# MCU.net
KiCad netlist of a schematic drawn in Altium Designer
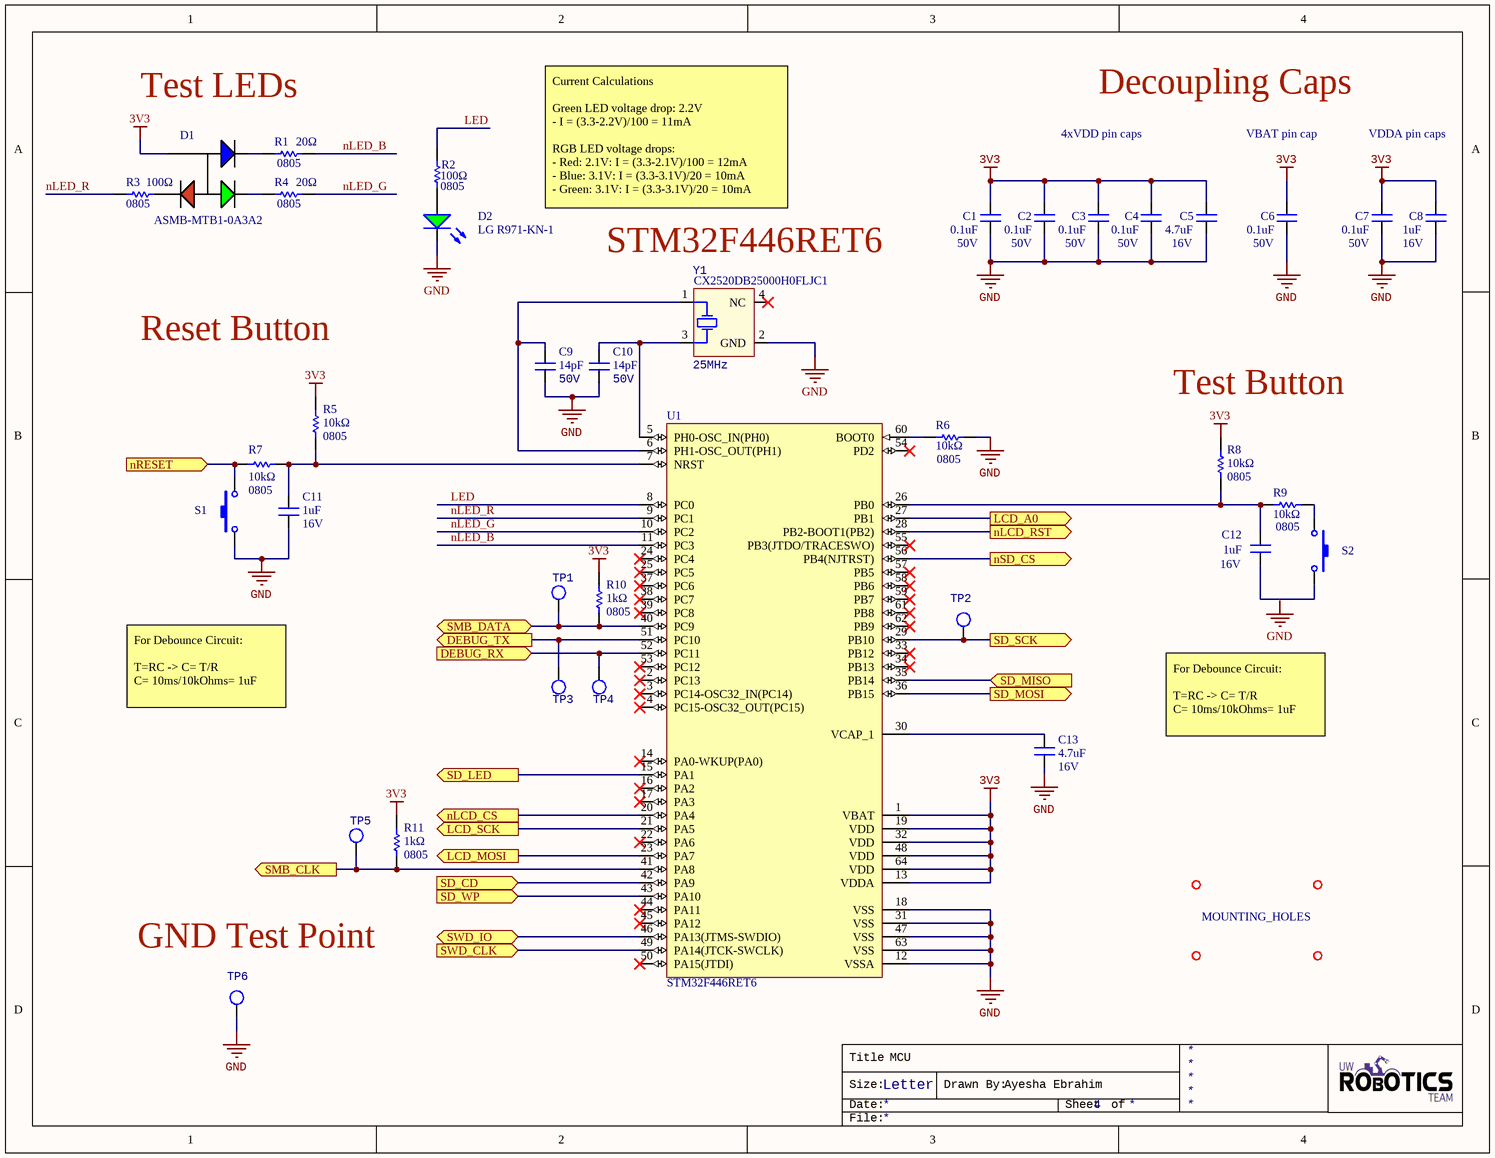
[diagram p0: MCU.SchDoc]

(export (version "E")
  (design (tool "Eeschema 10.0.6"))
  (components
    (comp (ref "C1")
      (value "0.1uF")
      (footprint "CAPC2012X140N")
      (description "CAP CER 0.1UF 50V X7R 0805")
      (fields
        (field (name "TOLERANCE") "10%")
        (field (name "VOLTAGE RATING") "50V")
        (field (name "Comment") "CAP_0.1uF_50V_0805")
      )
      (libsource (lib "UWRT_Schematic_Library_2020") (part "CAP_0.1uF_50V_0805"))
    )
    (comp (ref "C2")
      (value "0.1uF")
      (footprint "CAPC2012X140N")
      (description "CAP CER 0.1UF 50V X7R 0805")
      (fields
        (field (name "TOLERANCE") "10%")
        (field (name "VOLTAGE RATING") "50V")
        (field (name "Comment") "CAP_0.1uF_50V_0805")
      )
      (libsource (lib "UWRT_Schematic_Library_2020") (part "CAP_0.1uF_50V_0805"))
    )
    (comp (ref "C3")
      (value "0.1uF")
      (footprint "CAPC2012X140N")
      (description "CAP CER 0.1UF 50V X7R 0805")
      (fields
        (field (name "TOLERANCE") "10%")
        (field (name "VOLTAGE RATING") "50V")
        (field (name "Comment") "CAP_0.1uF_50V_0805")
      )
      (libsource (lib "UWRT_Schematic_Library_2020") (part "CAP_0.1uF_50V_0805"))
    )
    (comp (ref "C4")
      (value "0.1uF")
      (footprint "CAPC2012X140N")
      (description "CAP CER 0.1UF 50V X7R 0805")
      (fields
        (field (name "TOLERANCE") "10%")
        (field (name "VOLTAGE RATING") "50V")
        (field (name "Comment") "CAP_0.1uF_50V_0805")
      )
      (libsource (lib "UWRT_Schematic_Library_2020") (part "CAP_0.1uF_50V_0805"))
    )
    (comp (ref "C5")
      (value "4.7uF")
      (footprint "CAPC2012X140N")
      (description "CAP CER 4.7UF 16V X5R 0805")
      (fields
        (field (name "TOLERANCE") "10%")
        (field (name "VOLTAGE RATING") "16V")
        (field (name "Comment") "CAP_4.7uF_16V_0805")
      )
      (libsource (lib "UWRT_Schematic_Library_2020") (part "CAP_4.7uF_16V_0805"))
    )
    (comp (ref "C6")
      (value "0.1uF")
      (footprint "CAPC2012X140N")
      (description "CAP CER 0.1UF 50V X7R 0805")
      (fields
        (field (name "TOLERANCE") "10%")
        (field (name "VOLTAGE RATING") "50V")
        (field (name "Comment") "CAP_0.1uF_50V_0805")
      )
      (libsource (lib "UWRT_Schematic_Library_2020") (part "CAP_0.1uF_50V_0805"))
    )
    (comp (ref "C7")
      (value "0.1uF")
      (footprint "CAPC2012X140N")
      (description "CAP CER 0.1UF 50V X7R 0805")
      (fields
        (field (name "TOLERANCE") "10%")
        (field (name "VOLTAGE RATING") "50V")
        (field (name "Comment") "CAP_0.1uF_50V_0805")
      )
      (libsource (lib "UWRT_Schematic_Library_2020") (part "CAP_0.1uF_50V_0805"))
    )
    (comp (ref "C8")
      (value "1uF")
      (footprint "CAPC2012X140N")
      (description "CAP CER 1UF 16V X7R 0805")
      (fields
        (field (name "TOLERANCE") "10%")
        (field (name "VOLTAGE RATING") "16V")
        (field (name "Comment") "CAP_1uF_16V_0805")
      )
      (libsource (lib "UWRT_Schematic_Library_2020") (part "CAP_1uF_16V_0805"))
    )
    (comp (ref "C9")
      (value "14pF")
      (footprint "CAPC0603(1608)55_N")
      (description "Cap Ceramic 14pF 50V C0G 5% SMD 0603 125C Cardboard T/R")
      (fields
        (field (name "TOLERANCE") "5%")
        (field (name "VOLTAGE RATING (DC)") "50V")
        (field (name "Comment") "CL10C140JB8NNNC")
      )
      (libsource (lib "UWRT_Schematic_Library_2020") (part "CL10C140JB8NNNC"))
    )
    (comp (ref "C10")
      (value "14pF")
      (footprint "CAPC0603(1608)55_N")
      (description "Cap Ceramic 14pF 50V C0G 5% SMD 0603 125C Cardboard T/R")
      (fields
        (field (name "TOLERANCE") "5%")
        (field (name "VOLTAGE RATING (DC)") "50V")
        (field (name "Comment") "CL10C140JB8NNNC")
      )
      (libsource (lib "UWRT_Schematic_Library_2020") (part "CL10C140JB8NNNC"))
    )
    (comp (ref "C11")
      (value "1uF")
      (footprint "CAPC2012X140N")
      (description "CAP CER 1UF 16V X7R 0805")
      (fields
        (field (name "TOLERANCE") "10%")
        (field (name "VOLTAGE RATING") "16V")
        (field (name "Comment") "CAP_1uF_16V_0805")
      )
      (libsource (lib "UWRT_Schematic_Library_2020") (part "CAP_1uF_16V_0805"))
    )
    (comp (ref "C12")
      (value "1uF")
      (footprint "CAPC2012X140N")
      (description "CAP CER 1UF 16V X7R 0805")
      (fields
        (field (name "TOLERANCE") "10%")
        (field (name "VOLTAGE RATING") "16V")
        (field (name "Comment") "CAP_1uF_16V_0805")
      )
      (libsource (lib "UWRT_Schematic_Library_2020") (part "CAP_1uF_16V_0805"))
    )
    (comp (ref "C13")
      (value "4.7uF")
      (footprint "CAPC2012X140N")
      (description "CAP CER 4.7UF 16V X5R 0805")
      (fields
        (field (name "TOLERANCE") "10%")
        (field (name "VOLTAGE RATING") "16V")
        (field (name "Comment") "CAP_4.7uF_16V_0805")
      )
      (libsource (lib "UWRT_Schematic_Library_2020") (part "CAP_4.7uF_16V_0805"))
    )
    (comp (ref "D1")
      (value "LED_RGB")
      (footprint "LED_RGB")
      (description "LED RGB DIFFUSED 4PLCC SMD")
      (fields (field (name "MANUFACTURER PART NUMBER 1") "ASMB-MTB1-0A3A2"))
      (libsource (lib "UWRT_Schematic_Library_2020") (part "LED_RGB"))
    )
    (comp (ref "D2")
      (value "DIO_LED_G")
      (footprint "LED_0805_LINE")
      (description "LED GREEN DIFFUSED 0805 SMD")
      (fields (field (name "MANUFACTURER PART NUMBER 1") "LG R971-KN-1"))
      (libsource (lib "UWRT_Schematic_Library_2020") (part "DIO_LED_G"))
    )
    (comp (ref "MH1")
      (value "MOUNTING_HOLES")
      (footprint "MOUNTING_HOLE")
      (description "6cm x 6cm")
      (libsource (lib "UWRT_Schematic_Library_2020") (part "MOUNTING_HOLES"))
    )
    (comp (ref "MH2")
      (value "MOUNTING_HOLES")
      (footprint "MOUNTING_HOLE")
      (description "6cm x 6cm")
      (libsource (lib "UWRT_Schematic_Library_2020") (part "MOUNTING_HOLES"))
    )
    (comp (ref "MH3")
      (value "MOUNTING_HOLES")
      (footprint "MOUNTING_HOLE")
      (description "6cm x 6cm")
      (libsource (lib "UWRT_Schematic_Library_2020") (part "MOUNTING_HOLES"))
    )
    (comp (ref "MH4")
      (value "MOUNTING_HOLES")
      (footprint "MOUNTING_HOLE")
      (description "6cm x 6cm")
      (libsource (lib "UWRT_Schematic_Library_2020") (part "MOUNTING_HOLES"))
    )
    (comp (ref "R1")
      (value "20Ω")
      (footprint "RESC2012X60N")
      (description "RES SMD 20 OHM 1% 1/8W 0805")
      (fields
        (field (name "CASE CODE (IMPERIAL)") "0805")
        (field (name "TOLERANCE") "1%")
        (field (name "Comment") "RES_20Ω_0805")
      )
      (libsource (lib "UWRT_Schematic_Library_2020") (part "RES_20Ω_0805"))
    )
    (comp (ref "R2")
      (value "100Ω")
      (footprint "RESC2012X60N")
      (description "RES SMD 100 OHM 1% 1/8W 0805")
      (fields (field (name "CASE CODE (IMPERIAL)") "0805") (field (name "Comment") "RES_100Ω_0805"))
      (libsource (lib "UWRT_Schematic_Library_2020") (part "RES_100Ω_0805"))
    )
    (comp (ref "R3")
      (value "100Ω")
      (footprint "RESC2012X60N")
      (description "RES SMD 100 OHM 1% 1/8W 0805")
      (fields (field (name "CASE CODE (IMPERIAL)") "0805") (field (name "Comment") "RES_100Ω_0805"))
      (libsource (lib "UWRT_Schematic_Library_2020") (part "RES_100Ω_0805"))
    )
    (comp (ref "R4")
      (value "20Ω")
      (footprint "RESC2012X60N")
      (description "RES SMD 20 OHM 1% 1/8W 0805")
      (fields
        (field (name "CASE CODE (IMPERIAL)") "0805")
        (field (name "TOLERANCE") "1%")
        (field (name "Comment") "RES_20Ω_0805")
      )
      (libsource (lib "UWRT_Schematic_Library_2020") (part "RES_20Ω_0805"))
    )
    (comp (ref "R5")
      (value "10kΩ")
      (footprint "RESC2012X60N")
      (description "RES SMD 10K OHM 1% 1/8W 0805")
      (fields
        (field (name "CASE CODE (IMPERIAL)") "0805")
        (field (name "TOLERANCE") "1%")
        (field (name "Comment") "RES_10kΩ_0805")
      )
      (libsource (lib "UWRT_Schematic_Library_2020") (part "RES_10kΩ_0805"))
    )
    (comp (ref "R6")
      (value "10kΩ")
      (footprint "RESC2012X60N")
      (description "RES SMD 10K OHM 1% 1/8W 0805")
      (fields
        (field (name "CASE CODE (IMPERIAL)") "0805")
        (field (name "TOLERANCE") "1%")
        (field (name "Comment") "RES_10kΩ_0805")
      )
      (libsource (lib "UWRT_Schematic_Library_2020") (part "RES_10kΩ_0805"))
    )
    (comp (ref "R7")
      (value "10kΩ")
      (footprint "RESC2012X60N")
      (description "RES SMD 10K OHM 1% 1/8W 0805")
      (fields
        (field (name "CASE CODE (IMPERIAL)") "0805")
        (field (name "TOLERANCE") "1%")
        (field (name "Comment") "RES_10kΩ_0805")
      )
      (libsource (lib "UWRT_Schematic_Library_2020") (part "RES_10kΩ_0805"))
    )
    (comp (ref "R8")
      (value "10kΩ")
      (footprint "RESC2012X60N")
      (description "RES SMD 10K OHM 1% 1/8W 0805")
      (fields
        (field (name "CASE CODE (IMPERIAL)") "0805")
        (field (name "TOLERANCE") "1%")
        (field (name "Comment") "RES_10kΩ_0805")
      )
      (libsource (lib "UWRT_Schematic_Library_2020") (part "RES_10kΩ_0805"))
    )
    (comp (ref "R9")
      (value "10kΩ")
      (footprint "RESC2012X60N")
      (description "RES SMD 10K OHM 1% 1/8W 0805")
      (fields
        (field (name "CASE CODE (IMPERIAL)") "0805")
        (field (name "TOLERANCE") "1%")
        (field (name "Comment") "RES_10kΩ_0805")
      )
      (libsource (lib "UWRT_Schematic_Library_2020") (part "RES_10kΩ_0805"))
    )
    (comp (ref "R10")
      (value "1kΩ")
      (footprint "RESC2012X60N")
      (description "RES SMD 1K OHM 1% 1/8W 0805")
      (fields
        (field (name "CASE CODE (IMPERIAL)") "0805")
        (field (name "TOLERANCE") "1%")
        (field (name "Comment") "RES_1kΩ_0805")
      )
      (libsource (lib "UWRT_Schematic_Library_2020") (part "RES_1kΩ_0805"))
    )
    (comp (ref "R11")
      (value "1kΩ")
      (footprint "RESC2012X60N")
      (description "RES SMD 1K OHM 1% 1/8W 0805")
      (fields
        (field (name "CASE CODE (IMPERIAL)") "0805")
        (field (name "TOLERANCE") "1%")
        (field (name "Comment") "RES_1kΩ_0805")
      )
      (libsource (lib "UWRT_Schematic_Library_2020") (part "RES_1kΩ_0805"))
    )
    (comp (ref "S1")
      (value "SW_TACTILE")
      (footprint "B3U-1000P")
      (description "Tactile Switch (Grey)")
      (libsource (lib "UWRT_Schematic_Library_2020") (part "SW_TACTILE"))
    )
    (comp (ref "S2")
      (value "SW_TACTILE")
      (footprint "B3U-1000P")
      (description "Tactile Switch (Grey)")
      (libsource (lib "UWRT_Schematic_Library_2020") (part "SW_TACTILE"))
    )
    (comp (ref "TP1")
      (value "TESTPOINT_LOOP")
      (footprint "TESTPOINT_LOOP")
      (description "Loop testpoint through-hole pad")
      (libsource (lib "UWRT_Schematic_Library_2020") (part "TESTPOINT_LOOP"))
    )
    (comp (ref "TP2")
      (value "TESTPOINT_LOOP")
      (footprint "TESTPOINT_LOOP")
      (description "Loop testpoint through-hole pad")
      (libsource (lib "UWRT_Schematic_Library_2020") (part "TESTPOINT_LOOP"))
    )
    (comp (ref "TP3")
      (value "TESTPOINT_LOOP")
      (footprint "TESTPOINT_LOOP")
      (description "Loop testpoint through-hole pad")
      (libsource (lib "UWRT_Schematic_Library_2020") (part "TESTPOINT_LOOP"))
    )
    (comp (ref "TP4")
      (value "TESTPOINT_LOOP")
      (footprint "TESTPOINT_LOOP")
      (description "Loop testpoint through-hole pad")
      (libsource (lib "UWRT_Schematic_Library_2020") (part "TESTPOINT_LOOP"))
    )
    (comp (ref "TP5")
      (value "TESTPOINT_LOOP")
      (footprint "TESTPOINT_LOOP")
      (description "Loop testpoint through-hole pad")
      (libsource (lib "UWRT_Schematic_Library_2020") (part "TESTPOINT_LOOP"))
    )
    (comp (ref "TP6")
      (value "TESTPOINT_LOOP")
      (footprint "TESTPOINT_LOOP")
      (description "Loop testpoint through-hole pad")
      (libsource (lib "UWRT_Schematic_Library_2020") (part "TESTPOINT_LOOP"))
    )
    (comp (ref "U1")
      (value "STM32F446RET6")
      (footprint "STM-LQFP64_L")
      (libsource (lib "UWRT_Schematic_Library_2020") (part "MCU_STM32F446RET6"))
    )
    (comp (ref "Y1")
      (value "CRYSTAL_25MHZ")
      (footprint "SOIC254P1016X440-4N")
      (description "CRYSTAL 25.0000MHZ 12PF SMD")
      (fields
        (field (name "MANUFACTURER PART NUMBER 1") "CX2520DB25000H0FLJC1")
        (field (name "FREQUENCY") "25MHz")
      )
      (libsource (lib "UWRT_Schematic_Library_2020") (part "CRYSTAL_25MHZ"))
    )
  )
  (nets
    (net (code "1") (name "/DEBUG_RX") (class "Default")
      (node (ref "TP4") (pin "1") (pintype "passive"))
      (node (ref "U1") (pin "52") (pinfunction "PC11_52") (pintype "bidirectional"))
    )
    (net (code "2") (name "/DEBUG_TX") (class "Default")
      (node (ref "TP3") (pin "1") (pintype "passive"))
      (node (ref "U1") (pin "51") (pinfunction "PC10_51") (pintype "bidirectional"))
    )
    (net (code "3") (name "/LCD_A0") (class "Default")
      (node (ref "U1") (pin "27") (pinfunction "PB1_27") (pintype "bidirectional"))
    )
    (net (code "4") (name "/LCD_MOSI") (class "Default")
      (node (ref "U1") (pin "23") (pinfunction "PA7_23") (pintype "bidirectional"))
    )
    (net (code "5") (name "/LCD_SCK") (class "Default")
      (node (ref "U1") (pin "21") (pinfunction "PA5_21") (pintype "bidirectional"))
    )
    (net (code "6") (name "/LED") (class "Default")
      (node (ref "R2") (pin "2") (pinfunction "2_2") (pintype "passive"))
      (node (ref "U1") (pin "8") (pinfunction "PC0_8") (pintype "bidirectional"))
    )
    (net (code "7") (name "/SD_CD") (class "Default")
      (node (ref "U1") (pin "42") (pinfunction "PA9_42") (pintype "bidirectional"))
    )
    (net (code "8") (name "/SD_LED") (class "Default")
      (node (ref "U1") (pin "15") (pinfunction "PA1_15") (pintype "bidirectional"))
    )
    (net (code "9") (name "/SD_MISO") (class "Default")
      (node (ref "U1") (pin "35") (pinfunction "PB14_35") (pintype "bidirectional"))
    )
    (net (code "10") (name "/SD_MOSI") (class "Default")
      (node (ref "U1") (pin "36") (pinfunction "PB15_36") (pintype "bidirectional"))
    )
    (net (code "11") (name "/SD_SCK") (class "Default")
      (node (ref "TP2") (pin "1") (pintype "passive"))
      (node (ref "U1") (pin "29") (pinfunction "PB10_29") (pintype "bidirectional"))
    )
    (net (code "12") (name "/SD_WP") (class "Default")
      (node (ref "U1") (pin "43") (pinfunction "PA10_43") (pintype "bidirectional"))
    )
    (net (code "13") (name "/SMB_CLK") (class "Default")
      (node (ref "R11") (pin "1") (pinfunction "1_1") (pintype "passive"))
      (node (ref "TP5") (pin "1") (pintype "passive"))
      (node (ref "U1") (pin "41") (pinfunction "PA8_41") (pintype "bidirectional"))
    )
    (net (code "14") (name "/SMB_DATA") (class "Default")
      (node (ref "R10") (pin "1") (pinfunction "1_1") (pintype "passive"))
      (node (ref "TP1") (pin "1") (pintype "passive"))
      (node (ref "U1") (pin "40") (pinfunction "PC9_40") (pintype "bidirectional"))
    )
    (net (code "15") (name "/SWD_CLK") (class "Default")
      (node (ref "U1") (pin "49") (pinfunction "PA14(JTCK-SWCLK)_49") (pintype "bidirectional"))
    )
    (net (code "16") (name "/SWD_IO") (class "Default")
      (node (ref "U1") (pin "46") (pinfunction "PA13(JTMS-SWDIO)_46") (pintype "bidirectional"))
    )
    (net (code "17") (name "/nLCD_CS") (class "Default")
      (node (ref "U1") (pin "20") (pinfunction "PA4_20") (pintype "bidirectional"))
    )
    (net (code "18") (name "/nLCD_RST") (class "Default")
      (node (ref "U1") (pin "28") (pinfunction "PB2-BOOT1(PB2)_28") (pintype "bidirectional"))
    )
    (net (code "19") (name "/nLED_B") (class "Default")
      (node (ref "R1") (pin "2") (pinfunction "2_2") (pintype "passive"))
      (node (ref "U1") (pin "11") (pinfunction "PC3_11") (pintype "bidirectional"))
    )
    (net (code "20") (name "/nLED_G") (class "Default")
      (node (ref "R4") (pin "2") (pinfunction "2_2") (pintype "passive"))
      (node (ref "U1") (pin "10") (pinfunction "PC2_10") (pintype "bidirectional"))
    )
    (net (code "21") (name "/nLED_R") (class "Default")
      (node (ref "R3") (pin "1") (pinfunction "1_1") (pintype "passive"))
      (node (ref "U1") (pin "9") (pinfunction "PC1_9") (pintype "bidirectional"))
    )
    (net (code "22") (name "/nRESET") (class "Default")
      (node (ref "R7") (pin "1") (pinfunction "1_1") (pintype "passive"))
      (node (ref "S1") (pin "1") (pinfunction "1_1") (pintype "passive"))
    )
    (net (code "23") (name "/nSD_CS") (class "Default")
      (node (ref "U1") (pin "56") (pinfunction "PB4(NJTRST)_56") (pintype "bidirectional"))
    )
    (net (code "24") (name "3V3") (class "Default")
      (node (ref "C1") (pin "2") (pinfunction "2_2") (pintype "passive"))
      (node (ref "C2") (pin "2") (pinfunction "2_2") (pintype "passive"))
      (node (ref "C3") (pin "2") (pinfunction "2_2") (pintype "passive"))
      (node (ref "C4") (pin "2") (pinfunction "2_2") (pintype "passive"))
      (node (ref "C5") (pin "2") (pinfunction "2_2") (pintype "passive"))
      (node (ref "C6") (pin "2") (pinfunction "2_2") (pintype "passive"))
      (node (ref "C7") (pin "2") (pinfunction "2_2") (pintype "passive"))
      (node (ref "C8") (pin "2") (pinfunction "2_2") (pintype "passive"))
      (node (ref "D1") (pin "4") (pinfunction "9_4") (pintype "passive"))
      (node (ref "R10") (pin "2") (pinfunction "2_2") (pintype "passive"))
      (node (ref "R11") (pin "2") (pinfunction "2_2") (pintype "passive"))
      (node (ref "R5") (pin "2") (pinfunction "2_2") (pintype "passive"))
      (node (ref "R8") (pin "2") (pinfunction "2_2") (pintype "passive"))
      (node (ref "U1") (pin "1") (pinfunction "VBAT_1") (pintype "power_in"))
      (node (ref "U1") (pin "13") (pinfunction "VDDA_13") (pintype "power_in"))
      (node (ref "U1") (pin "19") (pinfunction "VDD_19") (pintype "power_in"))
      (node (ref "U1") (pin "32") (pinfunction "VDD_32") (pintype "power_in"))
      (node (ref "U1") (pin "48") (pinfunction "VDD_48") (pintype "power_in"))
      (node (ref "U1") (pin "64") (pinfunction "VDD_64") (pintype "power_in"))
    )
    (net (code "25") (name "GND") (class "Default")
      (node (ref "C1") (pin "1") (pinfunction "1_1") (pintype "passive"))
      (node (ref "C10") (pin "1") (pinfunction "1_1") (pintype "passive"))
      (node (ref "C11") (pin "1") (pinfunction "1_1") (pintype "passive"))
      (node (ref "C13") (pin "1") (pinfunction "1_1") (pintype "passive"))
      (node (ref "C2") (pin "1") (pinfunction "1_1") (pintype "passive"))
      (node (ref "C3") (pin "1") (pinfunction "1_1") (pintype "passive"))
      (node (ref "C4") (pin "1") (pinfunction "1_1") (pintype "passive"))
      (node (ref "C5") (pin "1") (pinfunction "1_1") (pintype "passive"))
      (node (ref "C6") (pin "1") (pinfunction "1_1") (pintype "passive"))
      (node (ref "C7") (pin "1") (pinfunction "1_1") (pintype "passive"))
      (node (ref "C8") (pin "1") (pinfunction "1_1") (pintype "passive"))
      (node (ref "C9") (pin "1") (pinfunction "1_1") (pintype "passive"))
      (node (ref "D2") (pin "2") (pinfunction "K_2") (pintype "passive"))
      (node (ref "R6") (pin "2") (pinfunction "2_2") (pintype "passive"))
      (node (ref "S1") (pin "2") (pinfunction "2_2") (pintype "passive"))
      (node (ref "TP6") (pin "1") (pintype "passive"))
      (node (ref "U1") (pin "12") (pinfunction "VSSA_12") (pintype "power_in"))
      (node (ref "U1") (pin "18") (pinfunction "VSS_18") (pintype "power_in"))
      (node (ref "U1") (pin "31") (pinfunction "VSS_31") (pintype "power_in"))
      (node (ref "U1") (pin "47") (pinfunction "VSS_47") (pintype "power_in"))
      (node (ref "U1") (pin "63") (pinfunction "VSS_63") (pintype "power_in"))
      (node (ref "Y1") (pin "2") (pinfunction "GND_2") (pintype "power_in"))
    )
    (net (code "26") (name "Net-(C12-Pad1)") (class "Default")
      (node (ref "C12") (pin "1") (pinfunction "1_1") (pintype "passive"))
      (node (ref "S2") (pin "2") (pinfunction "2_2") (pintype "passive"))
    )
    (net (code "27") (name "Net-(D1-10)") (class "Default")
      (node (ref "D1") (pin "3") (pinfunction "10_3") (pintype "passive"))
      (node (ref "R1") (pin "1") (pinfunction "1_1") (pintype "passive"))
    )
    (net (code "28") (name "Net-(D1-11)") (class "Default")
      (node (ref "D1") (pin "1") (pinfunction "11_1") (pintype "passive"))
      (node (ref "R3") (pin "2") (pinfunction "2_2") (pintype "passive"))
    )
    (net (code "29") (name "Net-(D1-12)") (class "Default")
      (node (ref "D1") (pin "2") (pinfunction "12_2") (pintype "passive"))
      (node (ref "R4") (pin "1") (pinfunction "1_1") (pintype "passive"))
    )
    (net (code "30") (name "Net-(D2-A)") (class "Default")
      (node (ref "D2") (pin "1") (pinfunction "A_1") (pintype "passive"))
      (node (ref "R2") (pin "1") (pinfunction "1_1") (pintype "passive"))
    )
    (net (code "31") (name "Net-(R9-Pad2)") (class "Default")
      (node (ref "R9") (pin "2") (pinfunction "2_2") (pintype "passive"))
      (node (ref "S2") (pin "1") (pinfunction "1_1") (pintype "passive"))
    )
    (net (code "32") (name "Net-(U1-BOOT0)") (class "Default")
      (node (ref "R6") (pin "1") (pinfunction "1_1") (pintype "passive"))
      (node (ref "U1") (pin "60") (pinfunction "BOOT0_60") (pintype "input"))
    )
    (net (code "33") (name "Net-(U1-NRST)") (class "Default")
      (node (ref "C11") (pin "2") (pinfunction "2_2") (pintype "passive"))
      (node (ref "R5") (pin "1") (pinfunction "1_1") (pintype "passive"))
      (node (ref "R7") (pin "2") (pinfunction "2_2") (pintype "passive"))
      (node (ref "U1") (pin "7") (pinfunction "NRST_7") (pintype "bidirectional"))
    )
    (net (code "34") (name "Net-(U1-PB0)") (class "Default")
      (node (ref "C12") (pin "2") (pinfunction "2_2") (pintype "passive"))
      (node (ref "R8") (pin "1") (pinfunction "1_1") (pintype "passive"))
      (node (ref "R9") (pin "1") (pinfunction "1_1") (pintype "passive"))
      (node (ref "U1") (pin "26") (pinfunction "PB0_26") (pintype "bidirectional"))
    )
    (net (code "35") (name "Net-(U1-PH0-OSC_IN(PH0))") (class "Default")
      (node (ref "C10") (pin "2") (pinfunction "2_2") (pintype "passive"))
      (node (ref "U1") (pin "5") (pinfunction "PH0-OSC_IN(PH0)_5") (pintype "bidirectional"))
      (node (ref "Y1") (pin "3") (pinfunction "HOT_3") (pintype "passive"))
    )
    (net (code "36") (name "Net-(U1-PH1-OSC_OUT(PH1))") (class "Default")
      (node (ref "C9") (pin "2") (pinfunction "2_2") (pintype "passive"))
      (node (ref "U1") (pin "6") (pinfunction "PH1-OSC_OUT(PH1)_6") (pintype "bidirectional"))
      (node (ref "Y1") (pin "1") (pinfunction "HOT_1") (pintype "passive"))
    )
    (net (code "37") (name "Net-(U1-VCAP_1)") (class "Default")
      (node (ref "C13") (pin "2") (pinfunction "2_2") (pintype "passive"))
      (node (ref "U1") (pin "30") (pinfunction "VCAP_1_30") (pintype "passive"))
    )
    (net (code "38") (name "unconnected-(U1-PA0-WKUP(PA0)-Pad14)") (class "Default")
      (node (ref "U1") (pin "14") (pinfunction "PA0-WKUP(PA0)_14") (pintype "bidirectional+no_connect"))
    )
    (net (code "39") (name "unconnected-(U1-PA2-Pad16)") (class "Default")
      (node (ref "U1") (pin "16") (pinfunction "PA2_16") (pintype "bidirectional+no_connect"))
    )
    (net (code "40") (name "unconnected-(U1-PA3-Pad17)") (class "Default")
      (node (ref "U1") (pin "17") (pinfunction "PA3_17") (pintype "bidirectional+no_connect"))
    )
    (net (code "41") (name "unconnected-(U1-PA6-Pad22)") (class "Default")
      (node (ref "U1") (pin "22") (pinfunction "PA6_22") (pintype "bidirectional+no_connect"))
    )
    (net (code "42") (name "unconnected-(U1-PA11-Pad44)") (class "Default")
      (node (ref "U1") (pin "44") (pinfunction "PA11_44") (pintype "bidirectional+no_connect"))
    )
    (net (code "43") (name "unconnected-(U1-PA12-Pad45)") (class "Default")
      (node (ref "U1") (pin "45") (pinfunction "PA12_45") (pintype "bidirectional+no_connect"))
    )
    (net (code "44") (name "unconnected-(U1-PA15(JTDI)-Pad50)") (class "Default")
      (node (ref "U1") (pin "50") (pinfunction "PA15(JTDI)_50") (pintype "bidirectional+no_connect"))
    )
    (net (code "45") (name "unconnected-(U1-PB3(JTDO{slash}TRACESWO)-Pad55)") (class "Default")
      (node (ref "U1") (pin "55") (pinfunction "PB3(JTDO/TRACESWO)_55") (pintype "bidirectional+no_connect"))
    )
    (net (code "46") (name "unconnected-(U1-PB5-Pad57)") (class "Default")
      (node (ref "U1") (pin "57") (pinfunction "PB5_57") (pintype "bidirectional+no_connect"))
    )
    (net (code "47") (name "unconnected-(U1-PB6-Pad58)") (class "Default")
      (node (ref "U1") (pin "58") (pinfunction "PB6_58") (pintype "bidirectional+no_connect"))
    )
    (net (code "48") (name "unconnected-(U1-PB7-Pad59)") (class "Default")
      (node (ref "U1") (pin "59") (pinfunction "PB7_59") (pintype "bidirectional+no_connect"))
    )
    (net (code "49") (name "unconnected-(U1-PB8-Pad61)") (class "Default")
      (node (ref "U1") (pin "61") (pinfunction "PB8_61") (pintype "bidirectional+no_connect"))
    )
    (net (code "50") (name "unconnected-(U1-PB9-Pad62)") (class "Default")
      (node (ref "U1") (pin "62") (pinfunction "PB9_62") (pintype "bidirectional+no_connect"))
    )
    (net (code "51") (name "unconnected-(U1-PB12-Pad33)") (class "Default")
      (node (ref "U1") (pin "33") (pinfunction "PB12_33") (pintype "bidirectional+no_connect"))
    )
    (net (code "52") (name "unconnected-(U1-PB13-Pad34)") (class "Default")
      (node (ref "U1") (pin "34") (pinfunction "PB13_34") (pintype "bidirectional+no_connect"))
    )
    (net (code "53") (name "unconnected-(U1-PC4-Pad24)") (class "Default")
      (node (ref "U1") (pin "24") (pinfunction "PC4_24") (pintype "bidirectional+no_connect"))
    )
    (net (code "54") (name "unconnected-(U1-PC5-Pad25)") (class "Default")
      (node (ref "U1") (pin "25") (pinfunction "PC5_25") (pintype "bidirectional+no_connect"))
    )
    (net (code "55") (name "unconnected-(U1-PC6-Pad37)") (class "Default")
      (node (ref "U1") (pin "37") (pinfunction "PC6_37") (pintype "bidirectional+no_connect"))
    )
    (net (code "56") (name "unconnected-(U1-PC7-Pad38)") (class "Default")
      (node (ref "U1") (pin "38") (pinfunction "PC7_38") (pintype "bidirectional+no_connect"))
    )
    (net (code "57") (name "unconnected-(U1-PC8-Pad39)") (class "Default")
      (node (ref "U1") (pin "39") (pinfunction "PC8_39") (pintype "bidirectional+no_connect"))
    )
    (net (code "58") (name "unconnected-(U1-PC12-Pad53)") (class "Default")
      (node (ref "U1") (pin "53") (pinfunction "PC12_53") (pintype "bidirectional+no_connect"))
    )
    (net (code "59") (name "unconnected-(U1-PC13-Pad2)") (class "Default")
      (node (ref "U1") (pin "2") (pinfunction "PC13_2") (pintype "bidirectional+no_connect"))
    )
    (net (code "60") (name "unconnected-(U1-PC14-OSC32_IN(PC14)-Pad3)") (class "Default")
      (node (ref "U1") (pin "3") (pinfunction "PC14-OSC32_IN(PC14)_3") (pintype "bidirectional+no_connect"))
    )
    (net (code "61") (name "unconnected-(U1-PC15-OSC32_OUT(PC15)-Pad4)") (class "Default")
      (node (ref "U1") (pin "4") (pinfunction "PC15-OSC32_OUT(PC15)_4") (pintype "bidirectional+no_connect"))
    )
    (net (code "62") (name "unconnected-(U1-PD2-Pad54)") (class "Default")
      (node (ref "U1") (pin "54") (pinfunction "PD2_54") (pintype "bidirectional+no_connect"))
    )
    (net (code "63") (name "unconnected-(Y1-NC-Pad4)") (class "Default")
      (node (ref "Y1") (pin "4") (pinfunction "NC_4") (pintype "passive+no_connect"))
    )
  )
)
